# Digital_and_PS.net
KiCad netlist of a schematic drawn in Altium Designer
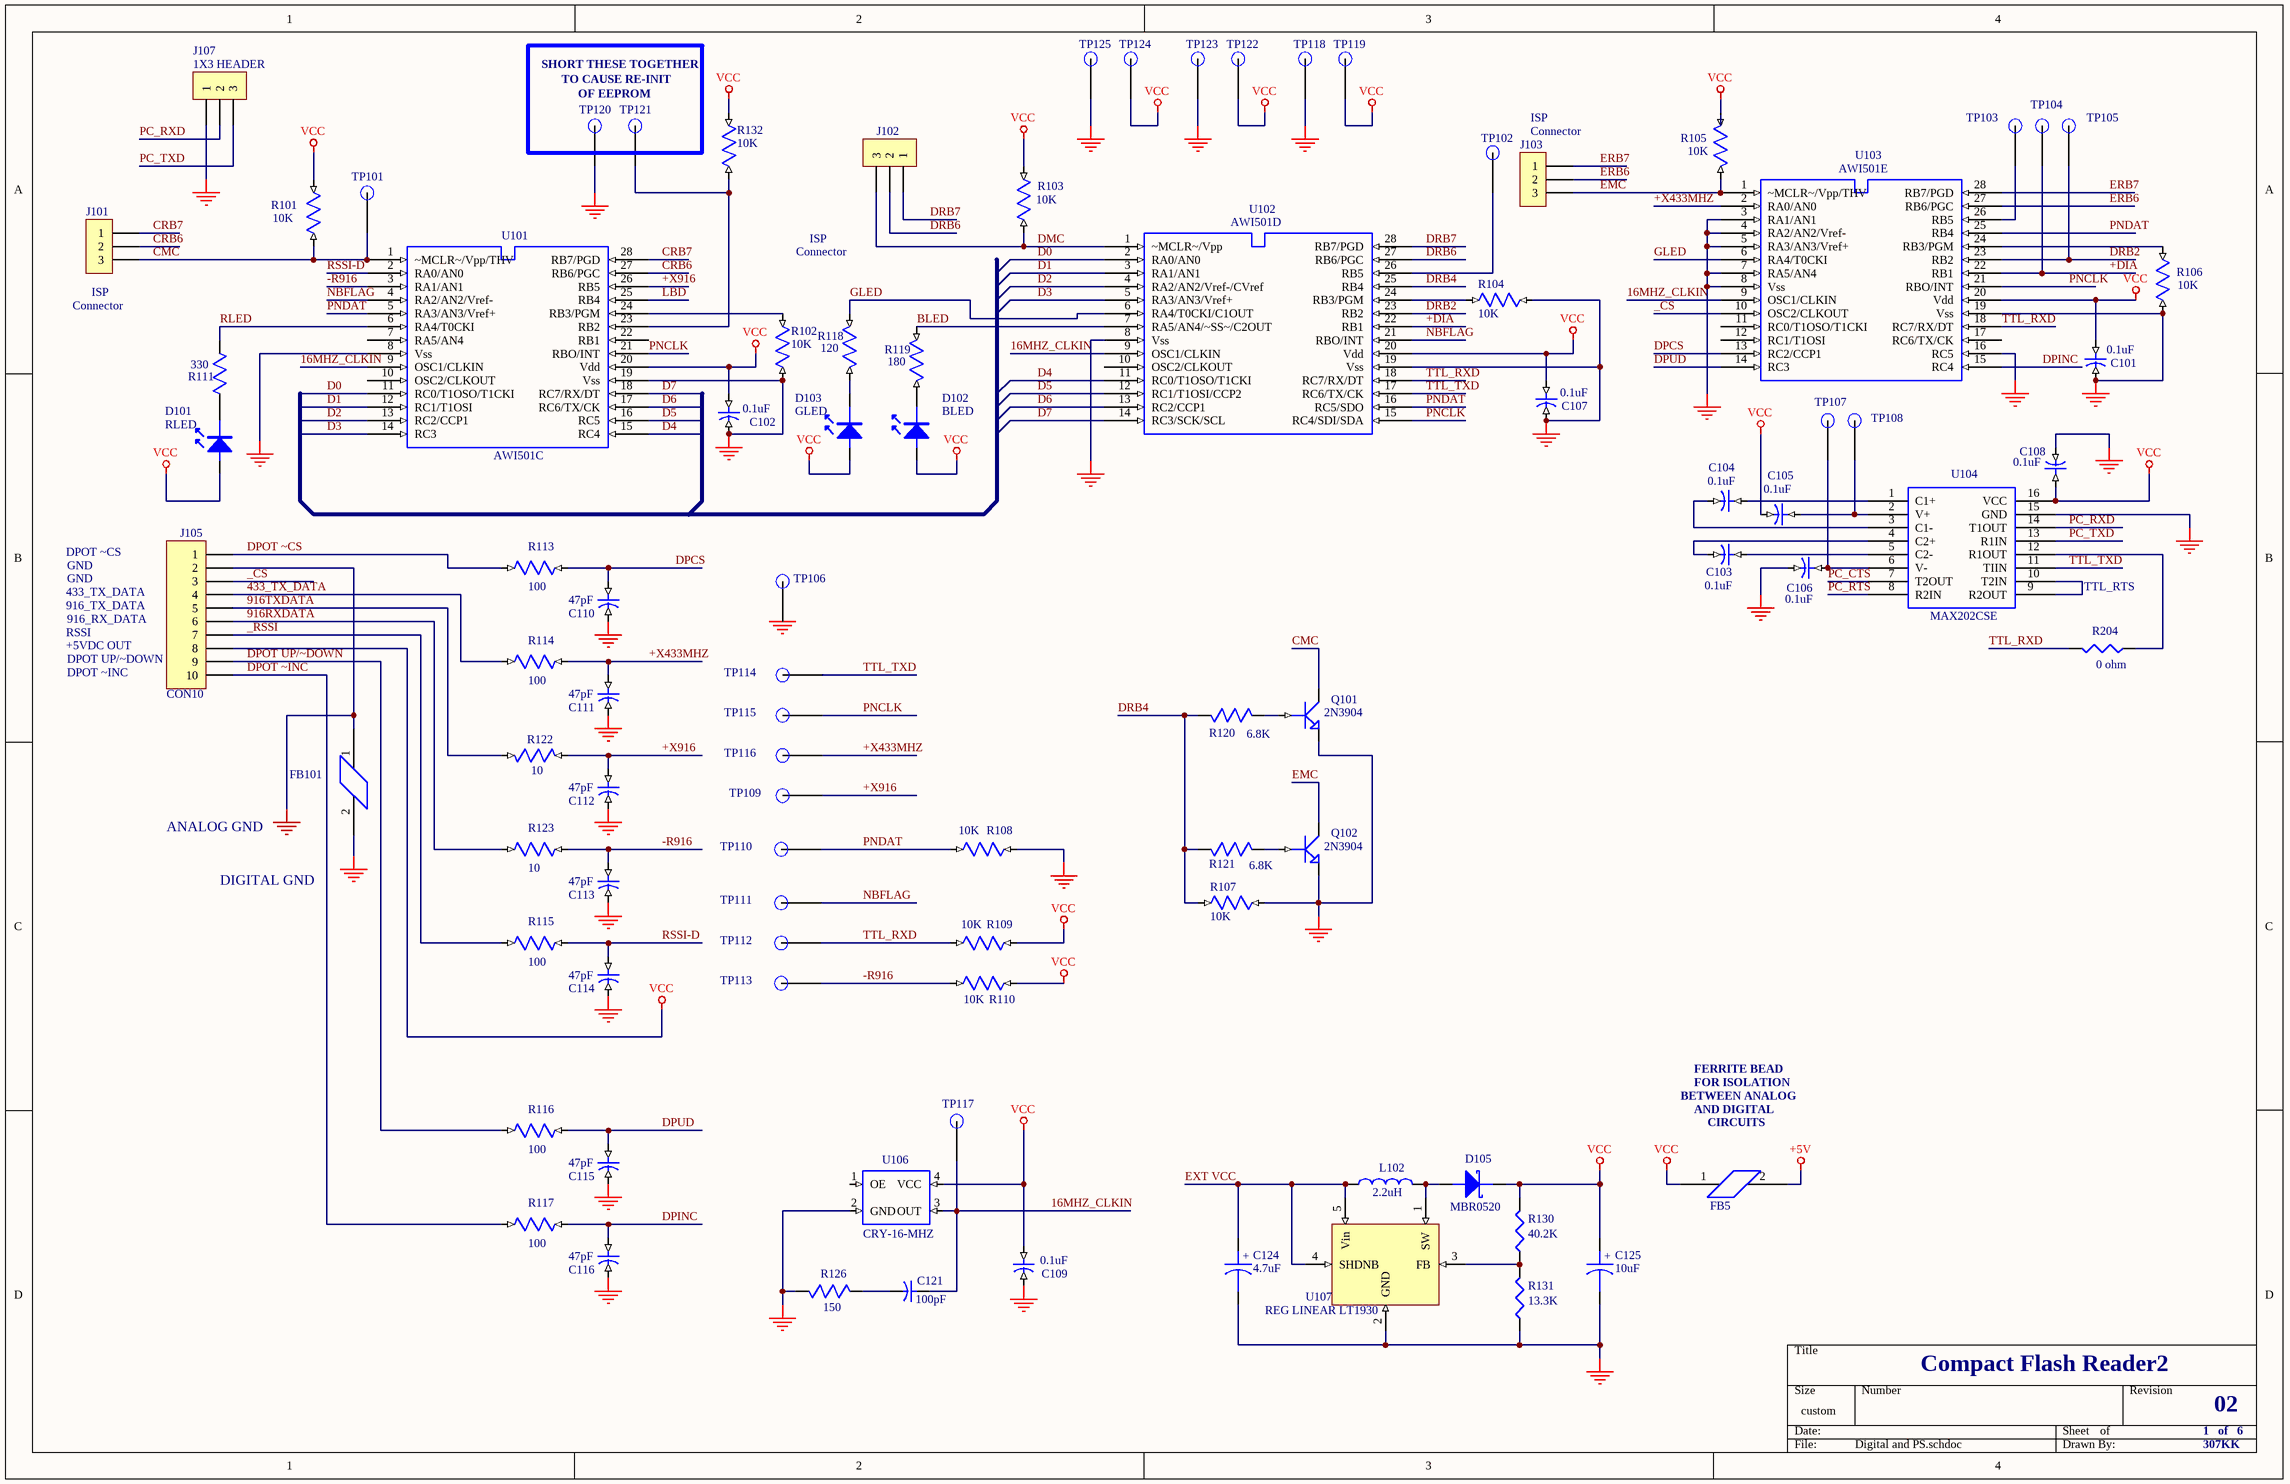
[diagram p0: Digital and PS.schdoc]

(export (version "E")
  (design (tool "Eeschema 10.0.6"))
  (components
    (comp (ref "C101") (value "0.1uF") (footprint "0603") (libsource (lib "*") (part "C_603")))
    (comp (ref "C102") (value "0.1uF") (footprint "0603") (libsource (lib "*") (part "C_603")))
    (comp (ref "C103") (value "0.1uF") (footprint "0603") (libsource (lib "") (part "C_603_1")))
    (comp (ref "C104") (value "0.1uF") (footprint "0603") (libsource (lib "") (part "C_603_1")))
    (comp (ref "C105") (value "0.1uF") (footprint "0603") (libsource (lib "") (part "C_603_1")))
    (comp (ref "C106") (value "0.1uF") (footprint "0603") (libsource (lib "") (part "C_603_1")))
    (comp (ref "C107") (value "0.1uF") (footprint "0603") (libsource (lib "*") (part "C_603")))
    (comp (ref "C108") (value "0.1uF") (footprint "0603") (libsource (lib "") (part "C_603_1")))
    (comp (ref "C109") (value "0.1uF") (footprint "0603") (libsource (lib "") (part "C_603_1")))
    (comp (ref "C110") (value "47pF") (footprint "0603") (libsource (lib "*") (part "C0603")))
    (comp (ref "C111") (value "47pF") (footprint "0603") (libsource (lib "*") (part "C0603")))
    (comp (ref "C112") (value "47pF") (footprint "0603") (libsource (lib "*") (part "C0603")))
    (comp (ref "C113") (value "47pF") (footprint "0603") (libsource (lib "*") (part "C0603")))
    (comp (ref "C114") (value "47pF") (footprint "0603") (libsource (lib "*") (part "C0603")))
    (comp (ref "C115") (value "47pF") (footprint "0603") (libsource (lib "*") (part "C0603")))
    (comp (ref "C116") (value "47pF") (footprint "0603") (libsource (lib "*") (part "C0603")))
    (comp (ref "C121") (value "100pF") (footprint "0603") (libsource (lib "*") (part "C_0603")))
    (comp (ref "C124")
      (value "4.7uF")
      (footprint "CAP A CASE")
      (description "Capacitor")
      (libsource (lib "*") (part "CAPACITOR POL"))
    )
    (comp (ref "C125")
      (value "10uF")
      (footprint "CAP A CASE")
      (description "Capacitor")
      (libsource (lib "*") (part "CAPACITOR POL"))
    )
    (comp (ref "D101") (value "RLED") (footprint "SOD123 DIODE") (libsource (lib "*") (part "LED")))
    (comp (ref "D102") (value "BLED") (footprint "SOD123 DIODE") (libsource (lib "*") (part "LED")))
    (comp (ref "D103") (value "GLED") (footprint "SOD123 DIODE") (libsource (lib "*") (part "LED")))
    (comp (ref "D105")
      (value "MBR0520")
      (footprint "SOD123")
      (description "Schottky Diode")
      (libsource (lib "*") (part "DIODE SCHOTTKY"))
    )
    (comp (ref "FB5") (value "FB") (footprint "0603") (libsource (lib "*") (part "FB_0603")))
    (comp (ref "FB101") (value "FB") (footprint "0603") (libsource (lib "*") (part "FB_0603")))
    (comp (ref "J101")
      (value "1X3 HEADER")
      (footprint "1X3 HEADER")
      (description "Connector")
      (libsource (lib "*") (part "CON3"))
    )
    (comp (ref "J102")
      (value "1X3 HEADER")
      (footprint "1X3 HEADER")
      (description "Connector")
      (libsource (lib "") (part "CON3_1"))
    )
    (comp (ref "J103")
      (value "1X3 HEADER")
      (footprint "1X3 HEADER")
      (description "Connector")
      (libsource (lib "*") (part "CON3"))
    )
    (comp (ref "J105")
      (value "CON10")
      (footprint "1X10 HEADER SPECIAL")
      (description "Connector")
      (libsource (lib "*") (part "CON10"))
    )
    (comp (ref "J107")
      (value "1X3 HEADER")
      (footprint "1X3 HEADER")
      (description "Connector")
      (libsource (lib "") (part "CON3_2"))
    )
    (comp (ref "L102")
      (value "2.2uH")
      (footprint "COIL BOURNS SDR7030-330M")
      (libsource (lib "*") (part "INDUCTOR1"))
    )
    (comp (ref "Q101")
      (value "2N3904")
      (footprint "SOT23 TRANS")
      (description "NPN Transistor")
      (libsource (lib "*") (part "NPN1"))
    )
    (comp (ref "Q102")
      (value "2N3904")
      (footprint "SOT23 TRANS")
      (description "NPN Transistor")
      (libsource (lib "*") (part "NPN1"))
    )
    (comp (ref "R101") (value "10K") (footprint "0603") (libsource (lib "*") (part "R_603")))
    (comp (ref "R102") (value "10K") (footprint "0603") (libsource (lib "*") (part "R_603")))
    (comp (ref "R103") (value "10K") (footprint "0603") (libsource (lib "*") (part "R_603")))
    (comp (ref "R104") (value "10K") (footprint "0603") (libsource (lib "*") (part "R_603")))
    (comp (ref "R105") (value "10K") (footprint "0603") (libsource (lib "*") (part "R_603")))
    (comp (ref "R106") (value "10K") (footprint "0603") (libsource (lib "*") (part "R_603")))
    (comp (ref "R107") (value "10K") (footprint "0603") (libsource (lib "*") (part "R_603")))
    (comp (ref "R108") (value "10K") (footprint "0603") (libsource (lib "*") (part "R_603")))
    (comp (ref "R109") (value "10K") (footprint "0603") (libsource (lib "*") (part "R_603")))
    (comp (ref "R110") (value "10K") (footprint "0603") (libsource (lib "*") (part "R_603")))
    (comp (ref "R111") (value "330") (footprint "0603") (libsource (lib "*") (part "R_0603")))
    (comp (ref "R113") (value "100") (footprint "0603") (libsource (lib "*") (part "R0603")))
    (comp (ref "R114") (value "100") (footprint "0603") (libsource (lib "*") (part "R0603")))
    (comp (ref "R115") (value "100") (footprint "0603") (libsource (lib "*") (part "R0603")))
    (comp (ref "R116") (value "100") (footprint "0603") (libsource (lib "*") (part "R0603")))
    (comp (ref "R117") (value "100") (footprint "0603") (libsource (lib "*") (part "R0603")))
    (comp (ref "R118") (value "120") (footprint "0603") (libsource (lib "*") (part "R0402")))
    (comp (ref "R119") (value "180") (footprint "0603") (libsource (lib "*") (part "R0402")))
    (comp (ref "R120") (value "6.8K") (footprint "0603") (libsource (lib "*") (part "R_0603")))
    (comp (ref "R121") (value "6.8K") (footprint "0603") (libsource (lib "*") (part "R_0603")))
    (comp (ref "R122") (value "10") (footprint "0603") (libsource (lib "*") (part "R_603")))
    (comp (ref "R123") (value "10") (footprint "0603") (libsource (lib "*") (part "R0603")))
    (comp (ref "R126") (value "150") (footprint "0603") (libsource (lib "*") (part "R_0603")))
    (comp (ref "R130") (value "40.2K") (footprint "0603") (libsource (lib "*") (part "RES1")))
    (comp (ref "R131") (value "13.3K") (footprint "0603") (libsource (lib "*") (part "RES1")))
    (comp (ref "R132") (value "10K") (footprint "0603") (libsource (lib "*") (part "R_603")))
    (comp (ref "R204") (value "0 ohm") (footprint "0603") (libsource (lib "*") (part "RES1")))
    (comp (ref "TP101") (value "TP") (footprint "TEST POINT PAD") (libsource (lib "*") (part "TESTPOINT_1")))
    (comp (ref "TP102") (value "TP") (footprint "TEST POINT PAD") (libsource (lib "*") (part "TESTPOINT_1")))
    (comp (ref "TP103") (value "TP") (footprint "TEST POINT PAD") (libsource (lib "*") (part "TESTPOINT_1")))
    (comp (ref "TP104") (value "TP") (footprint "TEST POINT PAD") (libsource (lib "*") (part "TESTPOINT_1")))
    (comp (ref "TP105") (value "TP") (footprint "TEST POINT PAD") (libsource (lib "*") (part "TESTPOINT_1")))
    (comp (ref "TP106") (value "TP") (footprint "TEST POINT PAD") (libsource (lib "*") (part "TESTPOINT_1")))
    (comp (ref "TP107") (value "TP") (footprint "TEST POINT PAD") (libsource (lib "*") (part "TESTPOINT_1")))
    (comp (ref "TP108") (value "TP") (footprint "TEST POINT PAD") (libsource (lib "*") (part "TESTPOINT_1")))
    (comp (ref "TP109") (value "TP") (footprint "TEST POINT PAD") (libsource (lib "*") (part "TESTPOINT_1")))
    (comp (ref "TP110") (value "TP") (footprint "TEST POINT PAD") (libsource (lib "*") (part "TESTPOINT_1")))
    (comp (ref "TP111") (value "TP") (footprint "TEST POINT PAD") (libsource (lib "*") (part "TESTPOINT_1")))
    (comp (ref "TP112") (value "TP") (footprint "TEST POINT PAD") (libsource (lib "*") (part "TESTPOINT_1")))
    (comp (ref "TP113") (value "TP") (footprint "TEST POINT PAD") (libsource (lib "*") (part "TESTPOINT_1")))
    (comp (ref "TP114") (value "TP") (footprint "TEST POINT PAD") (libsource (lib "*") (part "TESTPOINT_1")))
    (comp (ref "TP115") (value "TP") (footprint "TEST POINT PAD") (libsource (lib "*") (part "TESTPOINT_1")))
    (comp (ref "TP116") (value "TP") (footprint "TEST POINT PAD") (libsource (lib "*") (part "TESTPOINT_1")))
    (comp (ref "TP117") (value "TP") (footprint "TEST POINT PAD") (libsource (lib "*") (part "TESTPOINT_1")))
    (comp (ref "TP118") (value "TP") (footprint "TEST POINT PAD") (libsource (lib "*") (part "TESTPOINT_1")))
    (comp (ref "TP119") (value "TP") (footprint "TEST POINT PAD") (libsource (lib "*") (part "TESTPOINT_1")))
    (comp (ref "TP120") (value "TP") (footprint "TEST POINT PAD") (libsource (lib "*") (part "TESTPOINT_1")))
    (comp (ref "TP121") (value "TP") (footprint "TEST POINT PAD") (libsource (lib "*") (part "TESTPOINT_1")))
    (comp (ref "TP122") (value "TP") (footprint "TEST POINT PAD") (libsource (lib "*") (part "TESTPOINT_1")))
    (comp (ref "TP123") (value "TP") (footprint "TEST POINT PAD") (libsource (lib "*") (part "TESTPOINT_1")))
    (comp (ref "TP124") (value "TP") (footprint "TEST POINT PAD") (libsource (lib "*") (part "TESTPOINT_1")))
    (comp (ref "TP125") (value "TP") (footprint "TEST POINT PAD") (libsource (lib "*") (part "TESTPOINT_1")))
    (comp (ref "U101") (value "AWI501C") (footprint "SSOP28") (libsource (lib "*") (part "PIC16F870")))
    (comp (ref "U102") (value "AWI501D") (footprint "SSOP28") (libsource (lib "*") (part "PIC16F876A")))
    (comp (ref "U103") (value "AWI501E") (footprint "SSOP28") (libsource (lib "*") (part "PIC16F870")))
    (comp (ref "U104") (value "MAX202CSE") (footprint "SO16") (libsource (lib "*") (part "MAX202CSE")))
    (comp (ref "U106")
      (value "CRY-16-MHZ")
      (footprint "SMT OSCILLATOR")
      (libsource (lib "*") (part "CRY-SMD-5-7"))
    )
    (comp (ref "U107")
      (value "REG LINEAR LT1930")
      (footprint "SOT23-5A")
      (libsource (lib "*") (part "REG LINEAR LT1930"))
    )
  )
  (nets
    (net (code "1") (name "+5V") (class "Default")
      (node (ref "FB5") (pin "2") (pinfunction "1_2") (pintype "passive"))
    )
    (net (code "2") (name "/+DIA") (class "Default")
      (node (ref "TP104") (pin "1") (pinfunction "TP_1") (pintype "passive"))
      (node (ref "U102") (pin "22") (pinfunction "RB1_22") (pintype "input"))
      (node (ref "U103") (pin "22") (pinfunction "RB1_22") (pintype "input"))
    )
    (net (code "3") (name "/+X433MHZ") (class "Default")
      (node (ref "C111") (pin "1") (pinfunction "A_1") (pintype "input"))
      (node (ref "R114") (pin "2") (pinfunction "B_2") (pintype "input"))
      (node (ref "TP116") (pin "1") (pinfunction "TP_1") (pintype "passive"))
      (node (ref "U103") (pin "2") (pinfunction "RA0/AN0_2") (pintype "input"))
    )
    (net (code "4") (name "/+X916") (class "Default")
      (node (ref "C112") (pin "1") (pinfunction "A_1") (pintype "input"))
      (node (ref "R122") (pin "1") (pinfunction "A_1") (pintype "input"))
      (node (ref "TP109") (pin "1") (pinfunction "TP_1") (pintype "passive"))
      (node (ref "U101") (pin "26") (pinfunction "RB5_26") (pintype "input"))
    )
    (net (code "5") (name "/-R916") (class "Default")
      (node (ref "C113") (pin "1") (pinfunction "A_1") (pintype "input"))
      (node (ref "R110") (pin "2") (pinfunction "B_2") (pintype "input"))
      (node (ref "R123") (pin "2") (pinfunction "B_2") (pintype "input"))
      (node (ref "TP113") (pin "1") (pinfunction "TP_1") (pintype "passive"))
      (node (ref "U101") (pin "3") (pinfunction "RA1/AN1_3") (pintype "input"))
    )
    (net (code "6") (name "/16MHZ_CLKIN") (class "Default")
      (node (ref "C121") (pin "1") (pinfunction "A_1") (pintype "passive"))
      (node (ref "TP117") (pin "1") (pinfunction "TP_1") (pintype "passive"))
      (node (ref "U101") (pin "9") (pinfunction "OSC1/CLKIN_9") (pintype "input"))
      (node (ref "U102") (pin "9") (pinfunction "OSC1/CLKIN_9") (pintype "input"))
      (node (ref "U103") (pin "9") (pinfunction "OSC1/CLKIN_9") (pintype "input"))
      (node (ref "U106") (pin "3") (pinfunction "OUT_3") (pintype "input"))
    )
    (net (code "7") (name "/433_TX_DATA") (class "Default")
      (node (ref "J105") (pin "4") (pinfunction "4_4") (pintype "passive"))
      (node (ref "R114") (pin "1") (pinfunction "A_1") (pintype "input"))
    )
    (net (code "8") (name "/916RXDATA") (class "Default")
      (node (ref "J105") (pin "6") (pinfunction "6_6") (pintype "passive"))
      (node (ref "R123") (pin "1") (pinfunction "A_1") (pintype "input"))
    )
    (net (code "9") (name "/916TXDATA") (class "Default")
      (node (ref "J105") (pin "5") (pinfunction "5_5") (pintype "passive"))
      (node (ref "R122") (pin "2") (pinfunction "B_2") (pintype "input"))
    )
    (net (code "10") (name "/BLED") (class "Default")
      (node (ref "R119") (pin "2") (pinfunction "B_2") (pintype "input"))
      (node (ref "U102") (pin "7") (pinfunction "RA5/AN4/~SS~/C2OUT_7") (pintype "input"))
    )
    (net (code "11") (name "/CMC") (class "Default")
      (node (ref "J101") (pin "3") (pinfunction "3_3") (pintype "passive"))
      (node (ref "Q101") (pin "C") (pinfunction "C_C") (pintype "passive"))
      (node (ref "R101") (pin "2") (pinfunction "B_2") (pintype "input"))
      (node (ref "TP101") (pin "1") (pinfunction "TP_1") (pintype "passive"))
      (node (ref "U101") (pin "1") (pinfunction "~MCLR~/Vpp/THV_1") (pintype "input"))
    )
    (net (code "12") (name "/CRB6") (class "Default")
      (node (ref "J101") (pin "2") (pinfunction "2_2") (pintype "passive"))
      (node (ref "U101") (pin "27") (pinfunction "RB6/PGC_27") (pintype "input"))
    )
    (net (code "13") (name "/CRB7") (class "Default")
      (node (ref "J101") (pin "1") (pinfunction "1_1") (pintype "passive"))
      (node (ref "U101") (pin "28") (pinfunction "RB7/PGD_28") (pintype "input"))
    )
    (net (code "14") (name "/D0") (class "Default")
      (node (ref "U101") (pin "11") (pinfunction "RC0/T1OSO/T1CKI_11") (pintype "input"))
      (node (ref "U102") (pin "2") (pinfunction "RA0/AN0_2") (pintype "input"))
    )
    (net (code "15") (name "/D1") (class "Default")
      (node (ref "U101") (pin "12") (pinfunction "RC1/T1OSI_12") (pintype "input"))
      (node (ref "U102") (pin "3") (pinfunction "RA1/AN1_3") (pintype "input"))
    )
    (net (code "16") (name "/D2") (class "Default")
      (node (ref "U101") (pin "13") (pinfunction "RC2/CCP1_13") (pintype "input"))
      (node (ref "U102") (pin "4") (pinfunction "RA2/AN2/Vref-/CVref_4") (pintype "input"))
    )
    (net (code "17") (name "/D3") (class "Default")
      (node (ref "U101") (pin "14") (pinfunction "RC3_14") (pintype "input"))
      (node (ref "U102") (pin "5") (pinfunction "RA3/AN3/Vref+_5") (pintype "input"))
    )
    (net (code "18") (name "/D4") (class "Default")
      (node (ref "U101") (pin "15") (pinfunction "RC4_15") (pintype "input"))
      (node (ref "U102") (pin "11") (pinfunction "RC0/T1OSO/T1CKI_11") (pintype "input"))
    )
    (net (code "19") (name "/D5") (class "Default")
      (node (ref "U101") (pin "16") (pinfunction "RC5_16") (pintype "input"))
      (node (ref "U102") (pin "12") (pinfunction "RC1/T1OSI/CCP2_12") (pintype "input"))
    )
    (net (code "20") (name "/D6") (class "Default")
      (node (ref "U101") (pin "17") (pinfunction "RC6/TX/CK_17") (pintype "input"))
      (node (ref "U102") (pin "13") (pinfunction "RC2/CCP1_13") (pintype "input"))
    )
    (net (code "21") (name "/D7") (class "Default")
      (node (ref "U101") (pin "18") (pinfunction "RC7/RX/DT_18") (pintype "input"))
      (node (ref "U102") (pin "14") (pinfunction "RC3/SCK/SCL_14") (pintype "input"))
    )
    (net (code "22") (name "/DMC") (class "Default")
      (node (ref "J102") (pin "3") (pinfunction "3_3") (pintype "passive"))
      (node (ref "R103") (pin "2") (pinfunction "B_2") (pintype "input"))
      (node (ref "U102") (pin "1") (pinfunction "~MCLR~/Vpp_1") (pintype "input"))
    )
    (net (code "23") (name "/DPCS") (class "Default")
      (node (ref "C110") (pin "1") (pinfunction "A_1") (pintype "input"))
      (node (ref "R113") (pin "2") (pinfunction "B_2") (pintype "input"))
      (node (ref "U103") (pin "13") (pinfunction "RC2/CCP1_13") (pintype "input"))
    )
    (net (code "24") (name "/DPINC") (class "Default")
      (node (ref "C116") (pin "1") (pinfunction "A_1") (pintype "input"))
      (node (ref "R117") (pin "2") (pinfunction "B_2") (pintype "input"))
      (node (ref "U103") (pin "15") (pinfunction "RC4_15") (pintype "input"))
    )
    (net (code "25") (name "/DPOT UP{slash}~DOWN") (class "Default")
      (node (ref "J105") (pin "9") (pinfunction "9_9") (pintype "passive"))
      (node (ref "R116") (pin "1") (pinfunction "A_1") (pintype "input"))
    )
    (net (code "26") (name "/DPOT ~CS") (class "Default")
      (node (ref "J105") (pin "1") (pinfunction "1_1") (pintype "passive"))
      (node (ref "R113") (pin "1") (pinfunction "A_1") (pintype "input"))
    )
    (net (code "27") (name "/DPOT ~INC") (class "Default")
      (node (ref "J105") (pin "10") (pinfunction "10_10") (pintype "passive"))
      (node (ref "R117") (pin "1") (pinfunction "A_1") (pintype "input"))
    )
    (net (code "28") (name "/DPUD") (class "Default")
      (node (ref "C115") (pin "1") (pinfunction "A_1") (pintype "input"))
      (node (ref "R116") (pin "2") (pinfunction "B_2") (pintype "input"))
      (node (ref "U103") (pin "14") (pinfunction "RC3_14") (pintype "input"))
    )
    (net (code "29") (name "/DRB2") (class "Default")
      (node (ref "TP105") (pin "1") (pinfunction "TP_1") (pintype "passive"))
      (node (ref "U102") (pin "23") (pinfunction "RB2_23") (pintype "input"))
      (node (ref "U103") (pin "23") (pinfunction "RB2_23") (pintype "input"))
    )
    (net (code "30") (name "/DRB4") (class "Default")
      (node (ref "R107") (pin "1") (pinfunction "A_1") (pintype "input"))
      (node (ref "R120") (pin "1") (pinfunction "A_1") (pintype "passive"))
      (node (ref "R121") (pin "1") (pinfunction "A_1") (pintype "passive"))
      (node (ref "U102") (pin "25") (pinfunction "RB4_25") (pintype "input"))
    )
    (net (code "31") (name "/DRB6") (class "Default")
      (node (ref "J102") (pin "2") (pinfunction "2_2") (pintype "passive"))
      (node (ref "U102") (pin "27") (pinfunction "RB6/PGC_27") (pintype "input"))
    )
    (net (code "32") (name "/DRB7") (class "Default")
      (node (ref "J102") (pin "1") (pinfunction "1_1") (pintype "passive"))
      (node (ref "U102") (pin "28") (pinfunction "RB7/PGD_28") (pintype "input"))
    )
    (net (code "33") (name "/EMC") (class "Default")
      (node (ref "J103") (pin "3") (pinfunction "3_3") (pintype "passive"))
      (node (ref "Q102") (pin "C") (pinfunction "C_C") (pintype "passive"))
      (node (ref "R105") (pin "2") (pinfunction "B_2") (pintype "input"))
      (node (ref "U103") (pin "1") (pinfunction "~MCLR~/Vpp/THV_1") (pintype "input"))
    )
    (net (code "34") (name "/ERB6") (class "Default")
      (node (ref "J103") (pin "2") (pinfunction "2_2") (pintype "passive"))
      (node (ref "U103") (pin "27") (pinfunction "RB6/PGC_27") (pintype "input"))
    )
    (net (code "35") (name "/ERB7") (class "Default")
      (node (ref "J103") (pin "1") (pinfunction "1_1") (pintype "passive"))
      (node (ref "U103") (pin "28") (pinfunction "RB7/PGD_28") (pintype "input"))
    )
    (net (code "36") (name "/EXT VCC") (class "Default")
      (node (ref "C124") (pin "1") (pinfunction "1_1") (pintype "passive"))
      (node (ref "L102") (pin "1") (pinfunction "1_1") (pintype "passive"))
      (node (ref "U107") (pin "4") (pinfunction "SHDNB_4") (pintype "input"))
      (node (ref "U107") (pin "5") (pinfunction "Vin_5") (pintype "input"))
    )
    (net (code "37") (name "/GLED") (class "Default")
      (node (ref "R118") (pin "2") (pinfunction "B_2") (pintype "input"))
      (node (ref "U102") (pin "6") (pinfunction "RA4/T0CKI/C1OUT_6") (pintype "input"))
      (node (ref "U103") (pin "6") (pinfunction "RA4/T0CKI_6") (pintype "input"))
    )
    (net (code "38") (name "/LBD") (class "Default")
      (node (ref "U101") (pin "25") (pinfunction "RB4_25") (pintype "input"))
    )
    (net (code "39") (name "/NBFLAG") (class "Default")
      (node (ref "TP111") (pin "1") (pinfunction "TP_1") (pintype "passive"))
      (node (ref "U101") (pin "4") (pinfunction "RA2/AN2/Vref-_4") (pintype "input"))
      (node (ref "U102") (pin "21") (pinfunction "RBO/INT_21") (pintype "input"))
    )
    (net (code "40") (name "/PC_CTS") (class "Default")
      (node (ref "U104") (pin "7") (pinfunction "T2OUT_7") (pintype "passive"))
    )
    (net (code "41") (name "/PC_RTS") (class "Default")
      (node (ref "U104") (pin "8") (pinfunction "R2IN_8") (pintype "passive"))
    )
    (net (code "42") (name "/PC_RXD") (class "Default")
      (node (ref "J107") (pin "2") (pinfunction "2_2") (pintype "passive"))
      (node (ref "U104") (pin "14") (pinfunction "T1OUT_14") (pintype "passive"))
    )
    (net (code "43") (name "/PC_TXD") (class "Default")
      (node (ref "J107") (pin "3") (pinfunction "3_3") (pintype "passive"))
      (node (ref "U104") (pin "13") (pinfunction "R1IN_13") (pintype "passive"))
    )
    (net (code "44") (name "/PNCLK") (class "Default")
      (node (ref "TP115") (pin "1") (pinfunction "TP_1") (pintype "passive"))
      (node (ref "U101") (pin "21") (pinfunction "RBO/INT_21") (pintype "input"))
      (node (ref "U102") (pin "15") (pinfunction "RC4/SDI/SDA_15") (pintype "input"))
      (node (ref "U103") (pin "21") (pinfunction "RBO/INT_21") (pintype "input"))
    )
    (net (code "45") (name "/PNDAT") (class "Default")
      (node (ref "R108") (pin "2") (pinfunction "B_2") (pintype "input"))
      (node (ref "TP110") (pin "1") (pinfunction "TP_1") (pintype "passive"))
      (node (ref "U101") (pin "5") (pinfunction "RA3/AN3/Vref+_5") (pintype "input"))
      (node (ref "U102") (pin "16") (pinfunction "RC5/SDO_16") (pintype "input"))
      (node (ref "U103") (pin "25") (pinfunction "RB4_25") (pintype "input"))
    )
    (net (code "46") (name "/RLED") (class "Default")
      (node (ref "R111") (pin "2") (pinfunction "B_2") (pintype "passive"))
      (node (ref "U101") (pin "6") (pinfunction "RA4/T0CKI_6") (pintype "input"))
    )
    (net (code "47") (name "/RSSI-D") (class "Default")
      (node (ref "C114") (pin "1") (pinfunction "A_1") (pintype "input"))
      (node (ref "R115") (pin "2") (pinfunction "B_2") (pintype "input"))
      (node (ref "U101") (pin "2") (pinfunction "RA0/AN0_2") (pintype "input"))
    )
    (net (code "48") (name "/TTL_RXD") (class "Default")
      (node (ref "R109") (pin "2") (pinfunction "B_2") (pintype "input"))
      (node (ref "R204") (pin "2") (pinfunction "2_2") (pintype "passive"))
      (node (ref "TP112") (pin "1") (pinfunction "TP_1") (pintype "passive"))
      (node (ref "U102") (pin "18") (pinfunction "RC7/RX/DT_18") (pintype "input"))
      (node (ref "U103") (pin "18") (pinfunction "RC7/RX/DT_18") (pintype "input"))
    )
    (net (code "49") (name "/TTL_TXD") (class "Default")
      (node (ref "TP114") (pin "1") (pinfunction "TP_1") (pintype "passive"))
      (node (ref "U102") (pin "17") (pinfunction "RC6/TX/CK_17") (pintype "input"))
      (node (ref "U104") (pin "11") (pinfunction "TIIN_11") (pintype "passive"))
    )
    (net (code "50") (name "/_CS") (class "Default")
      (node (ref "J105") (pin "3") (pinfunction "3_3") (pintype "passive"))
      (node (ref "U103") (pin "10") (pinfunction "OSC2/CLKOUT_10") (pintype "input"))
    )
    (net (code "51") (name "/_RSSI") (class "Default")
      (node (ref "J105") (pin "7") (pinfunction "7_7") (pintype "passive"))
      (node (ref "R115") (pin "1") (pinfunction "A_1") (pintype "input"))
    )
    (net (code "52") (name "GND_COM") (class "Default")
      (node (ref "C101") (pin "2") (pinfunction "B_2") (pintype "input"))
      (node (ref "C102") (pin "2") (pinfunction "B_2") (pintype "input"))
      (node (ref "C106") (pin "2") (pinfunction "B_2") (pintype "input"))
      (node (ref "C107") (pin "2") (pinfunction "B_2") (pintype "input"))
      (node (ref "C108") (pin "2") (pinfunction "B_2") (pintype "input"))
      (node (ref "C109") (pin "2") (pinfunction "B_2") (pintype "input"))
      (node (ref "C110") (pin "2") (pinfunction "B_2") (pintype "input"))
      (node (ref "C111") (pin "2") (pinfunction "B_2") (pintype "input"))
      (node (ref "C112") (pin "2") (pinfunction "B_2") (pintype "input"))
      (node (ref "C113") (pin "2") (pinfunction "B_2") (pintype "input"))
      (node (ref "C114") (pin "2") (pinfunction "B_2") (pintype "input"))
      (node (ref "C115") (pin "2") (pinfunction "B_2") (pintype "input"))
      (node (ref "C116") (pin "2") (pinfunction "B_2") (pintype "input"))
      (node (ref "C124") (pin "2") (pinfunction "2_2") (pintype "passive"))
      (node (ref "C125") (pin "2") (pinfunction "2_2") (pintype "passive"))
      (node (ref "FB101") (pin "2") (pinfunction "1_2") (pintype "passive"))
      (node (ref "J107") (pin "1") (pinfunction "1_1") (pintype "passive"))
      (node (ref "Q101") (pin "E") (pinfunction "E_E") (pintype "passive"))
      (node (ref "Q102") (pin "E") (pinfunction "E_E") (pintype "passive"))
      (node (ref "R102") (pin "2") (pinfunction "B_2") (pintype "input"))
      (node (ref "R104") (pin "1") (pinfunction "A_1") (pintype "input"))
      (node (ref "R106") (pin "2") (pinfunction "B_2") (pintype "input"))
      (node (ref "R107") (pin "2") (pinfunction "B_2") (pintype "input"))
      (node (ref "R108") (pin "1") (pinfunction "A_1") (pintype "input"))
      (node (ref "R126") (pin "2") (pinfunction "B_2") (pintype "passive"))
      (node (ref "R131") (pin "1") (pinfunction "1_1") (pintype "passive"))
      (node (ref "TP106") (pin "1") (pinfunction "TP_1") (pintype "passive"))
      (node (ref "TP118") (pin "1") (pinfunction "TP_1") (pintype "passive"))
      (node (ref "TP120") (pin "1") (pinfunction "TP_1") (pintype "passive"))
      (node (ref "TP123") (pin "1") (pinfunction "TP_1") (pintype "passive"))
      (node (ref "TP125") (pin "1") (pinfunction "TP_1") (pintype "passive"))
      (node (ref "U101") (pin "19") (pinfunction "Vss_19") (pintype "input"))
      (node (ref "U101") (pin "8") (pinfunction "Vss_8") (pintype "input"))
      (node (ref "U102") (pin "19") (pinfunction "Vss_19") (pintype "input"))
      (node (ref "U102") (pin "8") (pinfunction "Vss_8") (pintype "input"))
      (node (ref "U103") (pin "16") (pinfunction "RC5_16") (pintype "input"))
      (node (ref "U103") (pin "19") (pinfunction "Vss_19") (pintype "input"))
      (node (ref "U103") (pin "3") (pinfunction "RA1/AN1_3") (pintype "input"))
      (node (ref "U103") (pin "4") (pinfunction "RA2/AN2/Vref-_4") (pintype "input"))
      (node (ref "U103") (pin "5") (pinfunction "RA3/AN3/Vref+_5") (pintype "input"))
      (node (ref "U103") (pin "7") (pinfunction "RA5/AN4_7") (pintype "input"))
      (node (ref "U103") (pin "8") (pinfunction "Vss_8") (pintype "input"))
      (node (ref "U104") (pin "15") (pinfunction "GND_15") (pintype "passive"))
      (node (ref "U106") (pin "2") (pinfunction "GND_2") (pintype "input"))
      (node (ref "U107") (pin "2") (pinfunction "GND_2") (pintype "input"))
    )
    (net (code "53") (name "GND_SIGNAL") (class "Default")
      (node (ref "FB101") (pin "1") (pinfunction "2_1") (pintype "passive"))
      (node (ref "J105") (pin "2") (pinfunction "2_2") (pintype "passive"))
    )
    (net (code "54") (name "Net-(C103-A)") (class "Default")
      (node (ref "C103") (pin "1") (pinfunction "A_1") (pintype "input"))
      (node (ref "U104") (pin "5") (pinfunction "C2-_5") (pintype "passive"))
    )
    (net (code "55") (name "Net-(C103-B)") (class "Default")
      (node (ref "C103") (pin "2") (pinfunction "B_2") (pintype "input"))
      (node (ref "U104") (pin "4") (pinfunction "C2+_4") (pintype "passive"))
    )
    (net (code "56") (name "Net-(C104-A)") (class "Default")
      (node (ref "C104") (pin "1") (pinfunction "A_1") (pintype "input"))
      (node (ref "U104") (pin "1") (pinfunction "C1+_1") (pintype "passive"))
    )
    (net (code "57") (name "Net-(C104-B)") (class "Default")
      (node (ref "C104") (pin "2") (pinfunction "B_2") (pintype "input"))
      (node (ref "U104") (pin "3") (pinfunction "C1-_3") (pintype "passive"))
    )
    (net (code "58") (name "Net-(C105-A)") (class "Default")
      (node (ref "C105") (pin "1") (pinfunction "A_1") (pintype "input"))
      (node (ref "TP108") (pin "1") (pinfunction "TP_1") (pintype "passive"))
      (node (ref "U104") (pin "2") (pinfunction "V+_2") (pintype "passive"))
    )
    (net (code "59") (name "Net-(C106-A)") (class "Default")
      (node (ref "C106") (pin "1") (pinfunction "A_1") (pintype "input"))
      (node (ref "TP107") (pin "1") (pinfunction "TP_1") (pintype "passive"))
      (node (ref "U104") (pin "6") (pinfunction "V-_6") (pintype "passive"))
    )
    (net (code "60") (name "Net-(C121-B)") (class "Default")
      (node (ref "C121") (pin "2") (pinfunction "B_2") (pintype "passive"))
      (node (ref "R126") (pin "1") (pinfunction "A_1") (pintype "passive"))
    )
    (net (code "61") (name "Net-(R102-A)") (class "Default")
      (node (ref "R102") (pin "1") (pinfunction "A_1") (pintype "input"))
      (node (ref "U101") (pin "24") (pinfunction "RB3/PGM_24") (pintype "input"))
    )
    (net (code "62") (name "Net-(R104-B)") (class "Default")
      (node (ref "R104") (pin "2") (pinfunction "B_2") (pintype "input"))
      (node (ref "U102") (pin "24") (pinfunction "RB3/PGM_24") (pintype "input"))
    )
    (net (code "63") (name "Net-(R106-A)") (class "Default")
      (node (ref "R106") (pin "1") (pinfunction "A_1") (pintype "input"))
      (node (ref "U103") (pin "24") (pinfunction "RB3/PGM_24") (pintype "input"))
    )
    (net (code "64") (name "Net-(R111-A)") (class "Default")
      (node (ref "D101") (pin "K") (pinfunction "K_K") (pintype "passive"))
      (node (ref "R111") (pin "1") (pinfunction "A_1") (pintype "passive"))
    )
    (net (code "65") (name "Net-(R118-A)") (class "Default")
      (node (ref "D103") (pin "K") (pinfunction "K_K") (pintype "passive"))
      (node (ref "R118") (pin "1") (pinfunction "A_1") (pintype "input"))
    )
    (net (code "66") (name "Net-(R119-A)") (class "Default")
      (node (ref "D102") (pin "K") (pinfunction "K_K") (pintype "passive"))
      (node (ref "R119") (pin "1") (pinfunction "A_1") (pintype "input"))
    )
    (net (code "67") (name "Net-(R120-B)") (class "Default")
      (node (ref "Q101") (pin "B") (pinfunction "B_B") (pintype "input"))
      (node (ref "R120") (pin "2") (pinfunction "B_2") (pintype "passive"))
    )
    (net (code "68") (name "Net-(R121-B)") (class "Default")
      (node (ref "Q102") (pin "B") (pinfunction "B_B") (pintype "input"))
      (node (ref "R121") (pin "2") (pinfunction "B_2") (pintype "passive"))
    )
    (net (code "69") (name "Net-(R132-B)") (class "Default")
      (node (ref "R132") (pin "2") (pinfunction "B_2") (pintype "input"))
      (node (ref "TP121") (pin "1") (pinfunction "TP_1") (pintype "passive"))
      (node (ref "U101") (pin "23") (pinfunction "RB2_23") (pintype "input"))
    )
    (net (code "70") (name "Net-(TP102-TP)") (class "Default")
      (node (ref "TP102") (pin "1") (pinfunction "TP_1") (pintype "passive"))
      (node (ref "U102") (pin "26") (pinfunction "RB5_26") (pintype "input"))
    )
    (net (code "71") (name "Net-(TP103-TP)") (class "Default")
      (node (ref "TP103") (pin "1") (pinfunction "TP_1") (pintype "passive"))
      (node (ref "U103") (pin "26") (pinfunction "RB5_26") (pintype "input"))
    )
    (net (code "72") (name "Net-(U104-R1OUT)") (class "Default")
      (node (ref "R204") (pin "1") (pinfunction "1_1") (pintype "passive"))
      (node (ref "U104") (pin "12") (pinfunction "R1OUT_12") (pintype "passive"))
    )
    (net (code "73") (name "Net-(U104-R2OUT)") (class "Default")
      (node (ref "U104") (pin "10") (pinfunction "T2IN_10") (pintype "passive"))
      (node (ref "U104") (pin "9") (pinfunction "R2OUT_9") (pintype "passive"))
    )
    (net (code "74") (name "Net-(U107-FB)") (class "Default")
      (node (ref "R130") (pin "1") (pinfunction "1_1") (pintype "passive"))
      (node (ref "R131") (pin "2") (pinfunction "2_2") (pintype "passive"))
      (node (ref "U107") (pin "3") (pinfunction "FB_3") (pintype "input"))
    )
    (net (code "75") (name "Net-(U107-SW)") (class "Default")
      (node (ref "D105") (pin "A") (pinfunction "A_A") (pintype "passive"))
      (node (ref "L102") (pin "2") (pinfunction "2_2") (pintype "passive"))
      (node (ref "U107") (pin "1") (pinfunction "SW_1") (pintype "input"))
    )
    (net (code "76") (name "VCC") (class "Default")
      (node (ref "C101") (pin "1") (pinfunction "A_1") (pintype "input"))
      (node (ref "C102") (pin "1") (pinfunction "A_1") (pintype "input"))
      (node (ref "C105") (pin "2") (pinfunction "B_2") (pintype "input"))
      (node (ref "C107") (pin "1") (pinfunction "A_1") (pintype "input"))
      (node (ref "C108") (pin "1") (pinfunction "A_1") (pintype "input"))
      (node (ref "C109") (pin "1") (pinfunction "A_1") (pintype "input"))
      (node (ref "C125") (pin "1") (pinfunction "1_1") (pintype "passive"))
      (node (ref "D101") (pin "A") (pinfunction "A_A") (pintype "passive"))
      (node (ref "D102") (pin "A") (pinfunction "A_A") (pintype "passive"))
      (node (ref "D103") (pin "A") (pinfunction "A_A") (pintype "passive"))
      (node (ref "D105") (pin "K") (pinfunction "K_K") (pintype "passive"))
      (node (ref "FB5") (pin "1") (pinfunction "2_1") (pintype "passive"))
      (node (ref "J105") (pin "8") (pinfunction "8_8") (pintype "passive"))
      (node (ref "R101") (pin "1") (pinfunction "A_1") (pintype "input"))
      (node (ref "R103") (pin "1") (pinfunction "A_1") (pintype "input"))
      (node (ref "R105") (pin "1") (pinfunction "A_1") (pintype "input"))
      (node (ref "R109") (pin "1") (pinfunction "A_1") (pintype "input"))
      (node (ref "R110") (pin "1") (pinfunction "A_1") (pintype "input"))
      (node (ref "R130") (pin "2") (pinfunction "2_2") (pintype "passive"))
      (node (ref "R132") (pin "1") (pinfunction "A_1") (pintype "input"))
      (node (ref "TP119") (pin "1") (pinfunction "TP_1") (pintype "passive"))
      (node (ref "TP122") (pin "1") (pinfunction "TP_1") (pintype "passive"))
      (node (ref "TP124") (pin "1") (pinfunction "TP_1") (pintype "passive"))
      (node (ref "U101") (pin "20") (pinfunction "Vdd_20") (pintype "input"))
      (node (ref "U102") (pin "20") (pinfunction "Vdd_20") (pintype "input"))
      (node (ref "U103") (pin "20") (pinfunction "Vdd_20") (pintype "input"))
      (node (ref "U104") (pin "16") (pinfunction "VCC_16") (pintype "passive"))
      (node (ref "U106") (pin "4") (pinfunction "VCC_4") (pintype "input"))
    )
    (net (code "77") (name "unconnected-(U101-OSC2{slash}CLKOUT-Pad10)") (class "Default")
      (node (ref "U101") (pin "10") (pinfunction "OSC2/CLKOUT_10") (pintype "input"))
    )
    (net (code "78") (name "unconnected-(U101-RA5{slash}AN4-Pad7)") (class "Default")
      (node (ref "U101") (pin "7") (pinfunction "RA5/AN4_7") (pintype "input"))
    )
    (net (code "79") (name "unconnected-(U101-RB1-Pad22)") (class "Default")
      (node (ref "U101") (pin "22") (pinfunction "RB1_22") (pintype "input"))
    )
    (net (code "80") (name "unconnected-(U102-OSC2{slash}CLKOUT-Pad10)") (class "Default")
      (node (ref "U102") (pin "10") (pinfunction "OSC2/CLKOUT_10") (pintype "input"))
    )
    (net (code "81") (name "unconnected-(U103-RC0{slash}T1OSO{slash}T1CKI-Pad11)") (class "Default")
      (node (ref "U103") (pin "11") (pinfunction "RC0/T1OSO/T1CKI_11") (pintype "input"))
    )
    (net (code "82") (name "unconnected-(U103-RC1{slash}T1OSI-Pad12)") (class "Default")
      (node (ref "U103") (pin "12") (pinfunction "RC1/T1OSI_12") (pintype "input"))
    )
    (net (code "83") (name "unconnected-(U103-RC6{slash}TX{slash}CK-Pad17)") (class "Default")
      (node (ref "U103") (pin "17") (pinfunction "RC6/TX/CK_17") (pintype "input"))
    )
    (net (code "84") (name "unconnected-(U106-OE-Pad1)") (class "Default")
      (node (ref "U106") (pin "1") (pinfunction "OE_1") (pintype "input"))
    )
  )
)
